# P09-USB_JTAG.net
KiCad netlist of a schematic drawn in Altium Designer
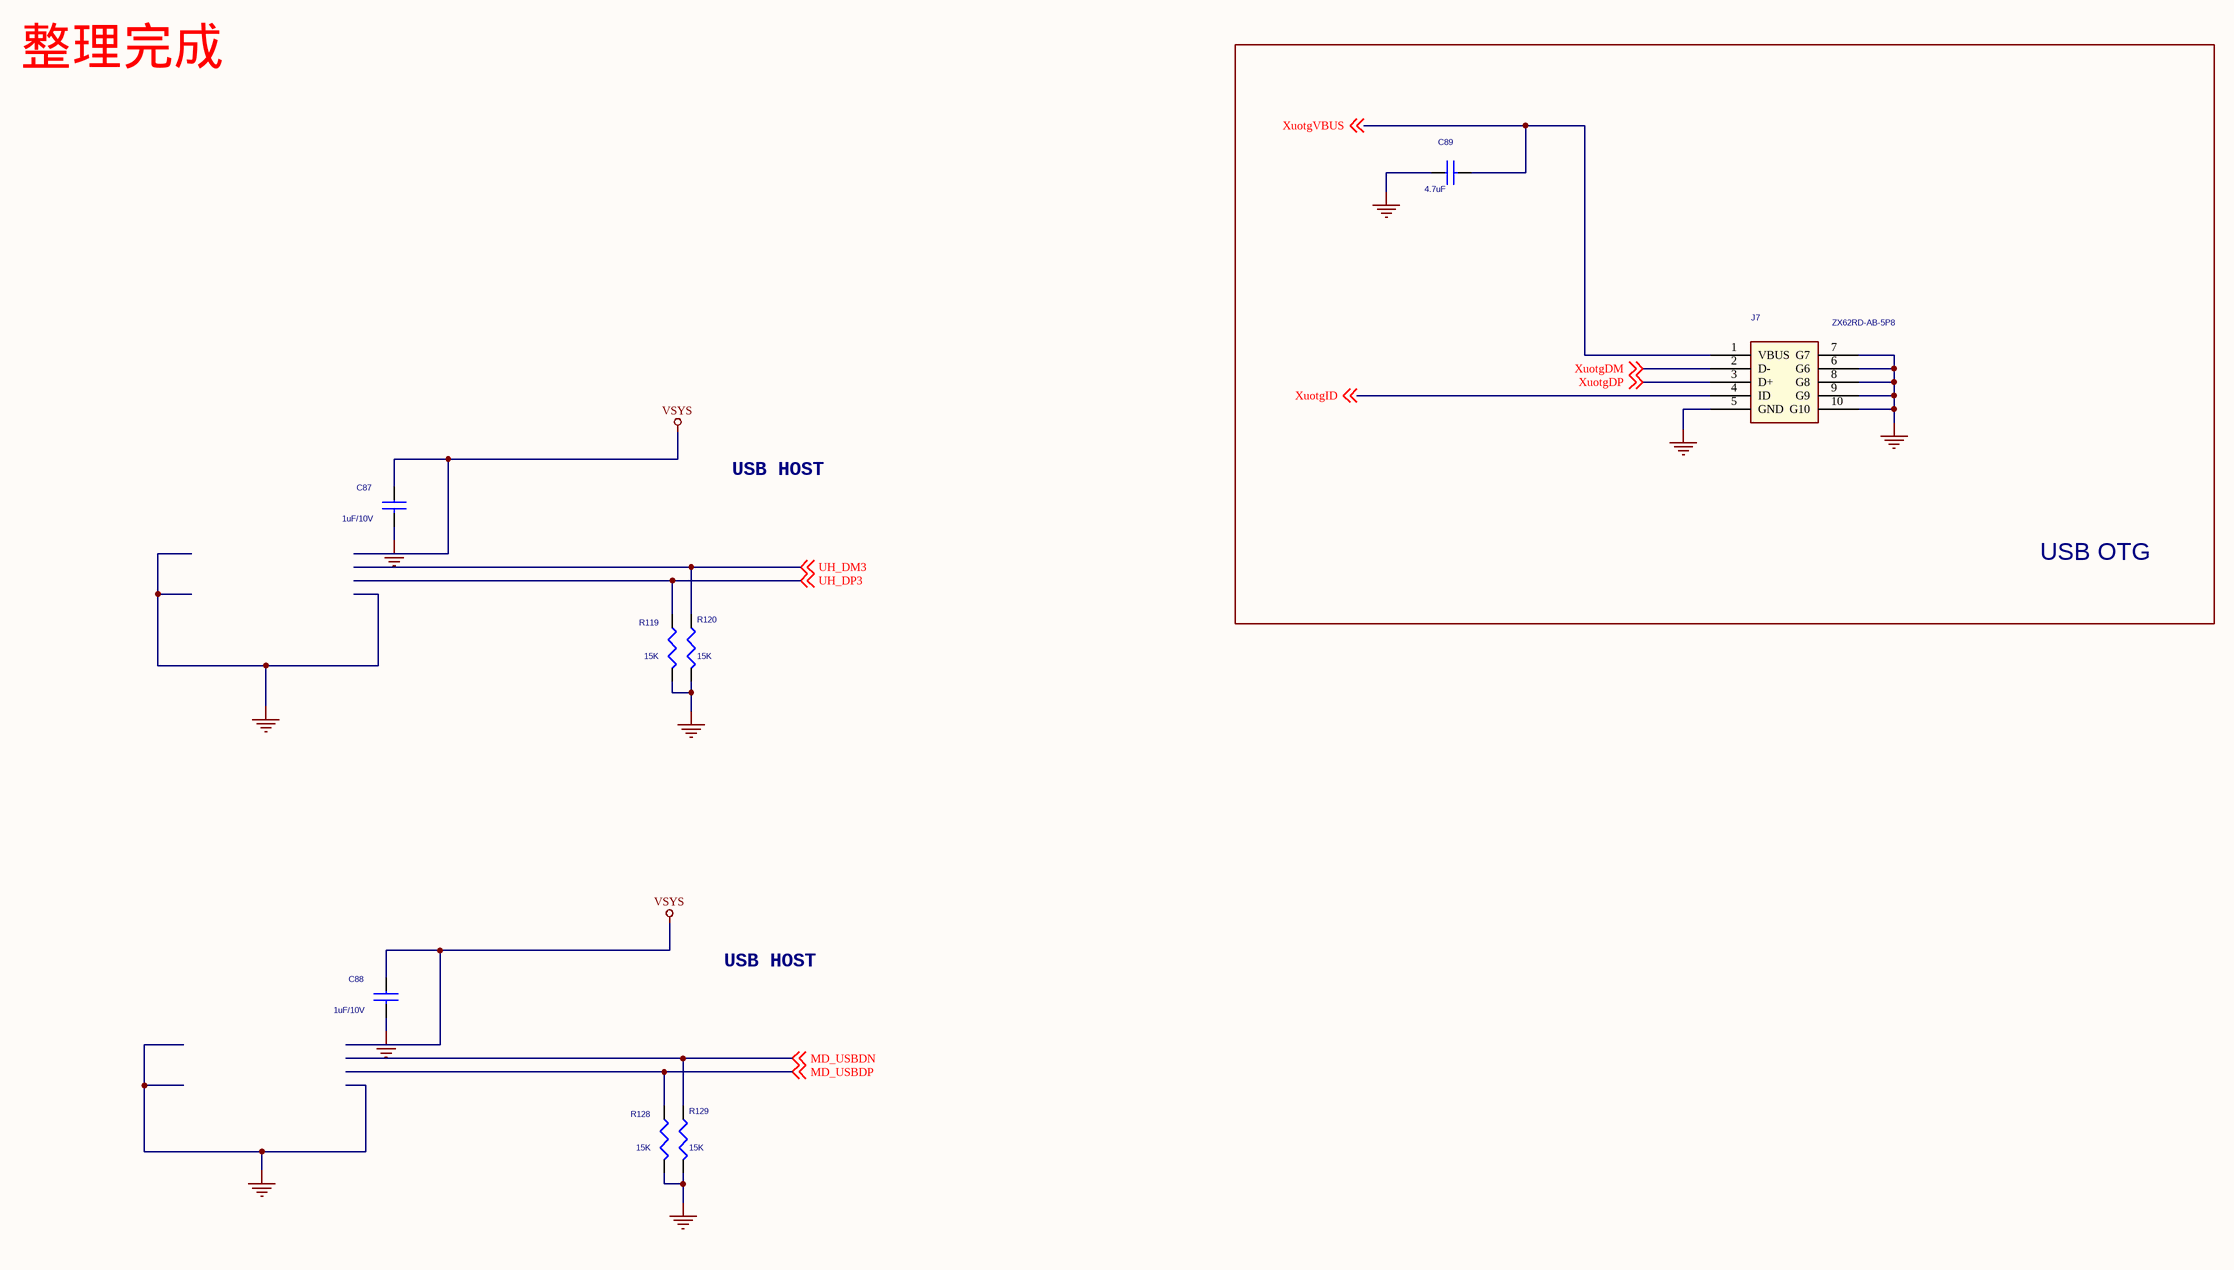
[diagram p0: P09-USB_JTAG.SchDoc]

(export (version "E")
  (design (tool "Eeschema 10.0.6"))
  (components
    (comp (ref "C87") (value "1uF/10V") (footprint "C0603-S") (libsource (lib "*") (part "C0603_0")))
    (comp (ref "C88") (value "1uF/10V") (footprint "C0603-S") (libsource (lib "*") (part "C0603_0")))
    (comp (ref "C89") (value "4.7uF") (footprint "C0603-S") (libsource (lib "*") (part "C1005")))
    (comp (ref "J7") (value "ZX62RD-AB-5P8") (libsource (lib "*") (part "ZX62RD-AB-5P8_3")))
    (comp (ref "R119") (value "15K") (footprint "R0603-S") (libsource (lib "*") (part "R1005_0")))
    (comp (ref "R120") (value "15K") (footprint "R0603-S") (libsource (lib "*") (part "R1005_0")))
    (comp (ref "R128") (value "15K") (footprint "R0603-S") (libsource (lib "*") (part "R1005_0")))
    (comp (ref "R129") (value "15K") (footprint "R0603-S") (libsource (lib "*") (part "R1005_0")))
  )
  (nets
    (net (code "1") (name "GND") (class "Default")
      (node (ref "C87") (pin "2") (pinfunction "2_2") (pintype "passive"))
      (node (ref "C88") (pin "2") (pinfunction "2_2") (pintype "passive"))
      (node (ref "C89") (pin "1") (pinfunction "1_1") (pintype "passive"))
      (node (ref "J7") (pin "10") (pinfunction "G10_10") (pintype "passive"))
      (node (ref "J7") (pin "5") (pinfunction "GND_5") (pintype "passive"))
      (node (ref "J7") (pin "6") (pinfunction "G6_6") (pintype "passive"))
      (node (ref "J7") (pin "7") (pinfunction "G7_7") (pintype "passive"))
      (node (ref "J7") (pin "8") (pinfunction "G8_8") (pintype "passive"))
      (node (ref "J7") (pin "9") (pinfunction "G9_9") (pintype "passive"))
      (node (ref "R119") (pin "1") (pinfunction "1_1") (pintype "passive"))
      (node (ref "R120") (pin "1") (pinfunction "1_1") (pintype "passive"))
      (node (ref "R128") (pin "1") (pinfunction "1_1") (pintype "passive"))
      (node (ref "R129") (pin "1") (pinfunction "1_1") (pintype "passive"))
    )
    (net (code "2") (name "MD_USBDN") (class "Default")
      (node (ref "R129") (pin "2") (pinfunction "2_2") (pintype "passive"))
    )
    (net (code "3") (name "MD_USBDP") (class "Default")
      (node (ref "R128") (pin "2") (pinfunction "2_2") (pintype "passive"))
    )
    (net (code "4") (name "UH_DM3") (class "Default")
      (node (ref "R120") (pin "2") (pinfunction "2_2") (pintype "passive"))
    )
    (net (code "5") (name "UH_DP3") (class "Default")
      (node (ref "R119") (pin "2") (pinfunction "2_2") (pintype "passive"))
    )
    (net (code "6") (name "VSYS") (class "Default")
      (node (ref "C87") (pin "1") (pinfunction "1_1") (pintype "passive"))
      (node (ref "C88") (pin "1") (pinfunction "1_1") (pintype "passive"))
    )
    (net (code "7") (name "XuotgDM") (class "Default")
      (node (ref "J7") (pin "2") (pinfunction "D-_2") (pintype "passive"))
    )
    (net (code "8") (name "XuotgDP") (class "Default")
      (node (ref "J7") (pin "3") (pinfunction "D+_3") (pintype "passive"))
    )
    (net (code "9") (name "XuotgID") (class "Default")
      (node (ref "J7") (pin "4") (pinfunction "ID_4") (pintype "passive"))
    )
    (net (code "10") (name "XuotgVBUS") (class "Default")
      (node (ref "C89") (pin "2") (pinfunction "2_2") (pintype "passive"))
      (node (ref "J7") (pin "1") (pinfunction "VBUS_1") (pintype "passive"))
    )
  )
)
